# atmega328p_standalone.net
KiCad netlist of a schematic drawn in EAGLE
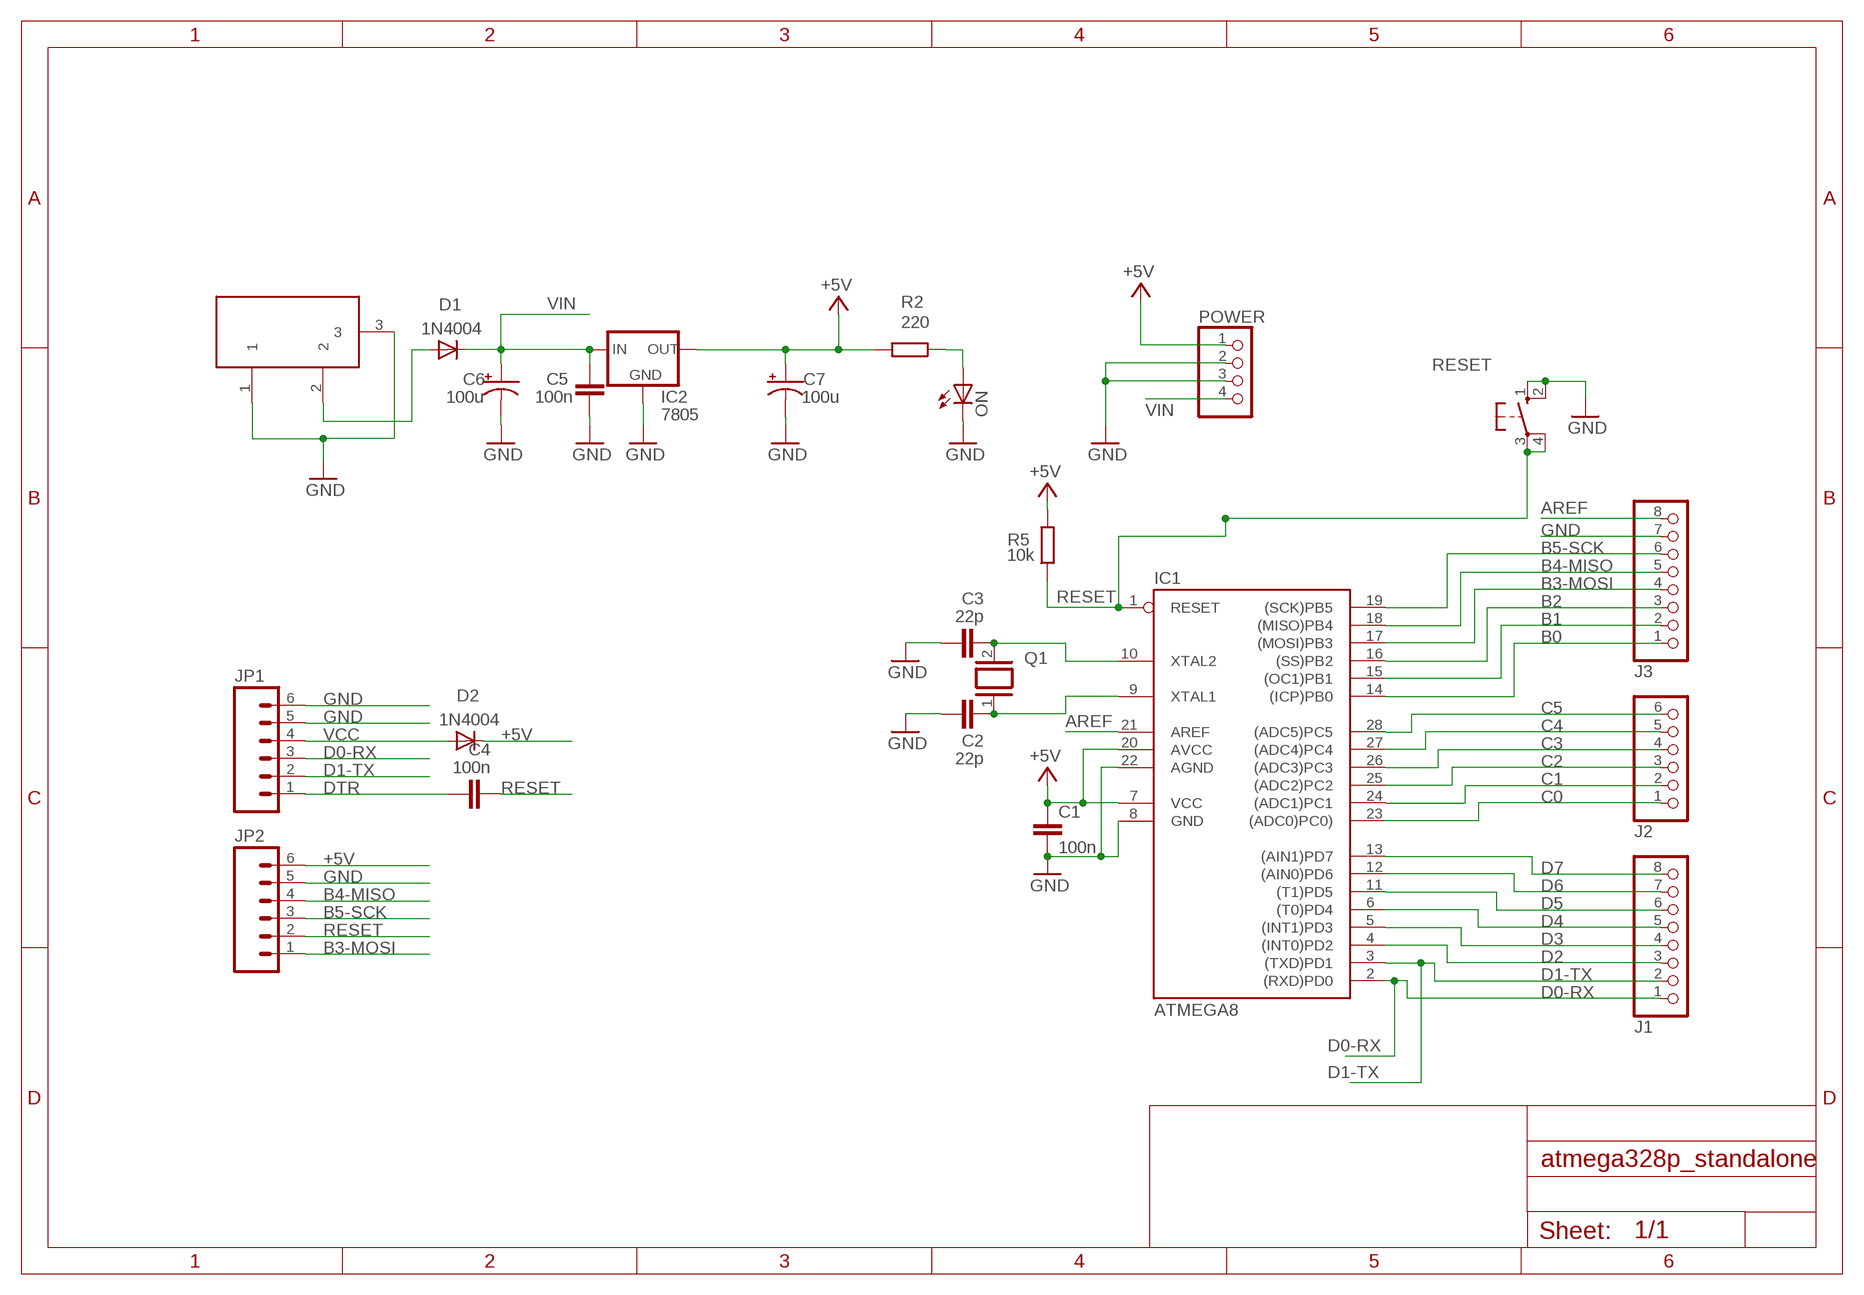
[diagram p0: schematic, sheet 1]

(export (version "E")
  (design (tool "Eeschema 10.0.6"))
  (components
    (comp (ref "C1")
      (value "100n")
      (footprint "eagle-import:C025-024X044")
      (libsource (lib "eagle-import") (part "C-EU025-024X044"))
    )
    (comp (ref "C2")
      (value "22p")
      (footprint "eagle-import:C025-024X044")
      (libsource (lib "eagle-import") (part "C-EU025-024X044"))
    )
    (comp (ref "C3")
      (value "22p")
      (footprint "eagle-import:C025-024X044")
      (libsource (lib "eagle-import") (part "C-EU025-024X044"))
    )
    (comp (ref "C4")
      (value "100n")
      (footprint "eagle-import:C025-024X044")
      (libsource (lib "eagle-import") (part "C-EU025-024X044"))
    )
    (comp (ref "C5")
      (value "100n")
      (footprint "eagle-import:C025-024X044")
      (libsource (lib "eagle-import") (part "C-EU025-024X044"))
    )
    (comp (ref "C6")
      (value "100u")
      (footprint "eagle-import:E2,5-7")
      (libsource (lib "eagle-import") (part "CPOL-USE2.5-7"))
    )
    (comp (ref "C7")
      (value "100u")
      (footprint "eagle-import:E2,5-7")
      (libsource (lib "eagle-import") (part "CPOL-USE2.5-7"))
    )
    (comp (ref "D1")
      (value "1N4004")
      (footprint "eagle-import:DO41-10")
      (libsource (lib "eagle-import") (part "1N4004"))
    )
    (comp (ref "D2")
      (value "1N4004")
      (footprint "eagle-import:DO41-10")
      (libsource (lib "eagle-import") (part "1N4004"))
    )
    (comp (ref "DC1")
      (value "DC21MMX")
      (footprint "eagle-import:DC-21MM")
      (libsource (lib "eagle-import") (part "DC21MMX"))
    )
    (comp (ref "IC1")
      (value "ATMEGA8")
      (footprint "eagle-import:DIL28-3")
      (libsource (lib "eagle-import") (part "AT90S4433P"))
    )
    (comp (ref "IC2")
      (value "7805")
      (footprint "eagle-import:78MXXS")
      (libsource (lib "eagle-import") (part "78MXXS"))
    )
    (comp (ref "J1")
      (value "PINHD-1X8")
      (footprint "eagle-import:1X08")
      (libsource (lib "eagle-import") (part "PINHD-1X8"))
    )
    (comp (ref "J2")
      (value "PINHD-1X6")
      (footprint "eagle-import:1X06")
      (libsource (lib "eagle-import") (part "PINHD-1X6"))
    )
    (comp (ref "J3")
      (value "PINHD-1X8")
      (footprint "eagle-import:1X08")
      (libsource (lib "eagle-import") (part "PINHD-1X8"))
    )
    (comp (ref "JP1")
      (value "M06SIP")
      (footprint "eagle-import:1X06")
      (libsource (lib "eagle-import") (part "M06SIP"))
    )
    (comp (ref "JP2")
      (value "M06SIP")
      (footprint "eagle-import:1X06")
      (libsource (lib "eagle-import") (part "M06SIP"))
    )
    (comp (ref "ON")
      (value "LED3MM")
      (footprint "eagle-import:LED3MM")
      (libsource (lib "eagle-import") (part "LED3MM"))
    )
    (comp (ref "POWER")
      (value "PINHD-1X4")
      (footprint "eagle-import:1X04")
      (libsource (lib "eagle-import") (part "PINHD-1X4"))
    )
    (comp (ref "Q1")
      (value "XTAL/S")
      (footprint "eagle-import:QS")
      (libsource (lib "eagle-import") (part "XTAL/S"))
    )
    (comp (ref "R2")
      (value "220")
      (footprint "eagle-import:0207_10")
      (libsource (lib "eagle-import") (part "R-EU_0207/10"))
    )
    (comp (ref "R5")
      (value "10k")
      (footprint "eagle-import:0207_10")
      (libsource (lib "eagle-import") (part "R-EU_0207/10"))
    )
    (comp (ref "RESET")
      (value "10-XX")
      (footprint "eagle-import:B3F-10XX")
      (libsource (lib "eagle-import") (part "10-XX"))
    )
  )
  (nets
    (net (code "1") (name "+5V") (class "Default")
      (node (ref "C1") (pin "1") (pinfunction "1_1") (pintype "passive"))
      (node (ref "C7") (pin "+") (pinfunction "+_+") (pintype "passive"))
      (node (ref "D2") (pin "C") (pinfunction "C_C") (pintype "passive"))
      (node (ref "IC1") (pin "20") (pinfunction "AVCC_20") (pintype "power_in"))
      (node (ref "IC1") (pin "7") (pinfunction "VCC_7") (pintype "power_in"))
      (node (ref "IC2") (pin "OUT") (pinfunction "OUT_OUT") (pintype "passive"))
      (node (ref "JP2") (pin "6") (pinfunction "6_6") (pintype "passive"))
      (node (ref "POWER") (pin "1") (pinfunction "1_1") (pintype "passive"))
      (node (ref "R2") (pin "2") (pinfunction "2_2") (pintype "passive"))
      (node (ref "R5") (pin "2") (pinfunction "2_2") (pintype "passive"))
    )
    (net (code "2") (name "/AREF") (class "Default")
      (node (ref "IC1") (pin "21") (pinfunction "AREF_21") (pintype "power_in"))
      (node (ref "J3") (pin "8") (pinfunction "8_8") (pintype "passive"))
    )
    (net (code "3") (name "/B0") (class "Default")
      (node (ref "IC1") (pin "14") (pinfunction "(ICP)PB0_14") (pintype "bidirectional"))
      (node (ref "J3") (pin "1") (pinfunction "1_1") (pintype "passive"))
    )
    (net (code "4") (name "/B1") (class "Default")
      (node (ref "IC1") (pin "15") (pinfunction "(OC1)PB1_15") (pintype "bidirectional"))
      (node (ref "J3") (pin "2") (pinfunction "2_2") (pintype "passive"))
    )
    (net (code "5") (name "/B2") (class "Default")
      (node (ref "IC1") (pin "16") (pinfunction "(SS)PB2_16") (pintype "bidirectional"))
      (node (ref "J3") (pin "3") (pinfunction "3_3") (pintype "passive"))
    )
    (net (code "6") (name "/B3-MOSI") (class "Default")
      (node (ref "IC1") (pin "17") (pinfunction "(MOSI)PB3_17") (pintype "bidirectional"))
      (node (ref "J3") (pin "4") (pinfunction "4_4") (pintype "passive"))
      (node (ref "JP2") (pin "1") (pinfunction "1_1") (pintype "passive"))
    )
    (net (code "7") (name "/B4-MISO") (class "Default")
      (node (ref "IC1") (pin "18") (pinfunction "(MISO)PB4_18") (pintype "bidirectional"))
      (node (ref "J3") (pin "5") (pinfunction "5_5") (pintype "passive"))
      (node (ref "JP2") (pin "4") (pinfunction "4_4") (pintype "passive"))
    )
    (net (code "8") (name "/B5-SCK") (class "Default")
      (node (ref "IC1") (pin "19") (pinfunction "(SCK)PB5_19") (pintype "bidirectional"))
      (node (ref "J3") (pin "6") (pinfunction "6_6") (pintype "passive"))
      (node (ref "JP2") (pin "3") (pinfunction "3_3") (pintype "passive"))
    )
    (net (code "9") (name "/C0") (class "Default")
      (node (ref "IC1") (pin "23") (pinfunction "(ADC0)PC0)_23") (pintype "bidirectional"))
      (node (ref "J2") (pin "1") (pinfunction "1_1") (pintype "passive"))
    )
    (net (code "10") (name "/C1") (class "Default")
      (node (ref "IC1") (pin "24") (pinfunction "(ADC1)PC1_24") (pintype "bidirectional"))
      (node (ref "J2") (pin "2") (pinfunction "2_2") (pintype "passive"))
    )
    (net (code "11") (name "/C2") (class "Default")
      (node (ref "IC1") (pin "25") (pinfunction "(ADC2)PC2_25") (pintype "bidirectional"))
      (node (ref "J2") (pin "3") (pinfunction "3_3") (pintype "passive"))
    )
    (net (code "12") (name "/C3") (class "Default")
      (node (ref "IC1") (pin "26") (pinfunction "(ADC3)PC3_26") (pintype "bidirectional"))
      (node (ref "J2") (pin "4") (pinfunction "4_4") (pintype "passive"))
    )
    (net (code "13") (name "/C4") (class "Default")
      (node (ref "IC1") (pin "27") (pinfunction "(ADC4)PC4_27") (pintype "bidirectional"))
      (node (ref "J2") (pin "5") (pinfunction "5_5") (pintype "passive"))
    )
    (net (code "14") (name "/C5") (class "Default")
      (node (ref "IC1") (pin "28") (pinfunction "(ADC5)PC5_28") (pintype "bidirectional"))
      (node (ref "J2") (pin "6") (pinfunction "6_6") (pintype "passive"))
    )
    (net (code "15") (name "/D0-RX") (class "Default")
      (node (ref "IC1") (pin "2") (pinfunction "(RXD)PD0_2") (pintype "bidirectional"))
      (node (ref "J1") (pin "1") (pinfunction "1_1") (pintype "passive"))
      (node (ref "JP1") (pin "3") (pinfunction "3_3") (pintype "passive"))
    )
    (net (code "16") (name "/D1-TX") (class "Default")
      (node (ref "IC1") (pin "3") (pinfunction "(TXD)PD1_3") (pintype "bidirectional"))
      (node (ref "J1") (pin "2") (pinfunction "2_2") (pintype "passive"))
      (node (ref "JP1") (pin "2") (pinfunction "2_2") (pintype "passive"))
    )
    (net (code "17") (name "/D2") (class "Default")
      (node (ref "IC1") (pin "4") (pinfunction "(INT0)PD2_4") (pintype "bidirectional"))
      (node (ref "J1") (pin "3") (pinfunction "3_3") (pintype "passive"))
    )
    (net (code "18") (name "/D3") (class "Default")
      (node (ref "IC1") (pin "5") (pinfunction "(INT1)PD3_5") (pintype "bidirectional"))
      (node (ref "J1") (pin "4") (pinfunction "4_4") (pintype "passive"))
    )
    (net (code "19") (name "/D4") (class "Default")
      (node (ref "IC1") (pin "6") (pinfunction "(T0)PD4_6") (pintype "bidirectional"))
      (node (ref "J1") (pin "5") (pinfunction "5_5") (pintype "passive"))
    )
    (net (code "20") (name "/D5") (class "Default")
      (node (ref "IC1") (pin "11") (pinfunction "(T1)PD5_11") (pintype "bidirectional"))
      (node (ref "J1") (pin "6") (pinfunction "6_6") (pintype "passive"))
    )
    (net (code "21") (name "/D6") (class "Default")
      (node (ref "IC1") (pin "12") (pinfunction "(AIN0)PD6_12") (pintype "bidirectional"))
      (node (ref "J1") (pin "7") (pinfunction "7_7") (pintype "passive"))
    )
    (net (code "22") (name "/D7") (class "Default")
      (node (ref "IC1") (pin "13") (pinfunction "(AIN1)PD7_13") (pintype "bidirectional"))
      (node (ref "J1") (pin "8") (pinfunction "8_8") (pintype "passive"))
    )
    (net (code "23") (name "/DTR") (class "Default")
      (node (ref "C4") (pin "1") (pinfunction "1_1") (pintype "passive"))
      (node (ref "JP1") (pin "1") (pinfunction "1_1") (pintype "passive"))
    )
    (net (code "24") (name "/RESET") (class "Default")
      (node (ref "C4") (pin "2") (pinfunction "2_2") (pintype "passive"))
      (node (ref "IC1") (pin "1") (pinfunction "RESET_1") (pintype "input"))
      (node (ref "JP2") (pin "2") (pinfunction "2_2") (pintype "passive"))
      (node (ref "R5") (pin "1") (pinfunction "1_1") (pintype "passive"))
      (node (ref "RESET") (pin "3") (pinfunction "P_3") (pintype "passive"))
      (node (ref "RESET") (pin "4") (pinfunction "P1_4") (pintype "passive"))
    )
    (net (code "25") (name "/VCC") (class "Default")
      (node (ref "D2") (pin "A") (pinfunction "A_A") (pintype "passive"))
      (node (ref "JP1") (pin "4") (pinfunction "4_4") (pintype "passive"))
    )
    (net (code "26") (name "/VIN") (class "Default")
      (node (ref "C5") (pin "2") (pinfunction "2_2") (pintype "passive"))
      (node (ref "C6") (pin "+") (pinfunction "+_+") (pintype "passive"))
      (node (ref "D1") (pin "C") (pinfunction "C_C") (pintype "passive"))
      (node (ref "IC2") (pin "IN") (pinfunction "IN_IN") (pintype "input"))
      (node (ref "POWER") (pin "4") (pinfunction "4_4") (pintype "passive"))
    )
    (net (code "27") (name "GND") (class "Default")
      (node (ref "C1") (pin "2") (pinfunction "2_2") (pintype "passive"))
      (node (ref "C2") (pin "1") (pinfunction "1_1") (pintype "passive"))
      (node (ref "C3") (pin "1") (pinfunction "1_1") (pintype "passive"))
      (node (ref "C5") (pin "1") (pinfunction "1_1") (pintype "passive"))
      (node (ref "C6") (pin "-") (pinfunction "-_-") (pintype "passive"))
      (node (ref "C7") (pin "-") (pinfunction "-_-") (pintype "passive"))
      (node (ref "DC1") (pin "1") (pinfunction "1_1") (pintype "power_in"))
      (node (ref "DC1") (pin "3") (pinfunction "3_3") (pintype "power_in"))
      (node (ref "IC1") (pin "22") (pinfunction "AGND_22") (pintype "power_in"))
      (node (ref "IC1") (pin "8") (pinfunction "GND_8") (pintype "power_in"))
      (node (ref "IC2") (pin "GND") (pinfunction "GND_GND") (pintype "input"))
      (node (ref "J3") (pin "7") (pinfunction "7_7") (pintype "passive"))
      (node (ref "JP1") (pin "5") (pinfunction "5_5") (pintype "passive"))
      (node (ref "JP1") (pin "6") (pinfunction "6_6") (pintype "passive"))
      (node (ref "JP2") (pin "5") (pinfunction "5_5") (pintype "passive"))
      (node (ref "ON") (pin "K") (pinfunction "C_K") (pintype "passive"))
      (node (ref "POWER") (pin "2") (pinfunction "2_2") (pintype "passive"))
      (node (ref "POWER") (pin "3") (pinfunction "3_3") (pintype "passive"))
      (node (ref "RESET") (pin "1") (pinfunction "S_1") (pintype "passive"))
      (node (ref "RESET") (pin "2") (pinfunction "S1_2") (pintype "passive"))
    )
    (net (code "28") (name "Net-(D1-PadA)") (class "Default")
      (node (ref "D1") (pin "A") (pinfunction "A_A") (pintype "passive"))
      (node (ref "DC1") (pin "2") (pinfunction "2_2") (pintype "power_in"))
    )
    (net (code "29") (name "Net-(IC1-XTAL1)") (class "Default")
      (node (ref "C2") (pin "2") (pinfunction "2_2") (pintype "passive"))
      (node (ref "IC1") (pin "9") (pinfunction "XTAL1_9") (pintype "bidirectional"))
      (node (ref "Q1") (pin "1") (pinfunction "1_1") (pintype "passive"))
    )
    (net (code "30") (name "Net-(IC1-XTAL2)") (class "Default")
      (node (ref "C3") (pin "2") (pinfunction "2_2") (pintype "passive"))
      (node (ref "IC1") (pin "10") (pinfunction "XTAL2_10") (pintype "bidirectional"))
      (node (ref "Q1") (pin "2") (pinfunction "2_2") (pintype "passive"))
    )
    (net (code "31") (name "Net-(ON-PadA)") (class "Default")
      (node (ref "ON") (pin "A") (pinfunction "A_A") (pintype "passive"))
      (node (ref "R2") (pin "1") (pinfunction "1_1") (pintype "passive"))
    )
  )
)
